# v1_0.net
KiCad netlist of a schematic drawn in Altium Designer
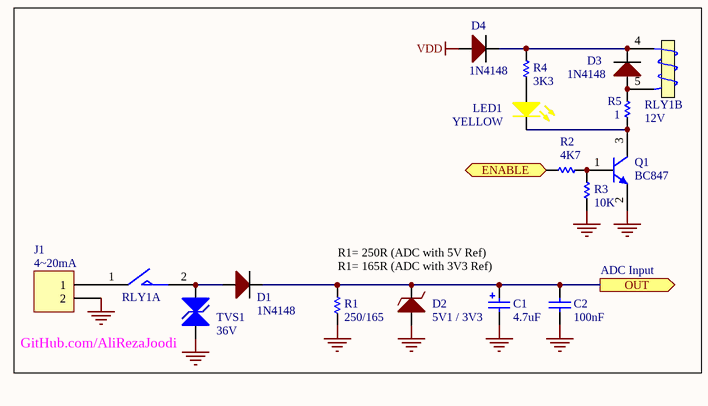
[diagram p0: v1.0.SchDoc]

(export (version "E")
  (design (tool "Eeschema 10.0.6"))
  (components
    (comp (ref "C1")
      (value "4.7uF")
      (footprint "CAPPR2.5-6.3x5")
      (description "Polarized Capacitor (Radial)")
      (fields (field (name "MANUFACTURER") "Generic Components") (field (name "PUBLISHER") "Altium Limited"))
      (libsource (lib "Miscellaneous Devices") (part "Cap Pol1"))
    )
    (comp (ref "C2")
      (value "100nF")
      (footprint "CAPNTO2.54-3.05x1.78A")
      (description "Capacitor")
      (fields (field (name "MANUFACTURER") "Generic Components") (field (name "PUBLISHER") "Altium Limited"))
      (libsource (lib "Miscellaneous Devices") (part "Cap"))
    )
    (comp (ref "D1")
      (value "1N4148")
      (footprint "D_THD_AXIAL0.3_DO-35")
      (description "Diode,")
      (libsource (lib "Passive") (part "Diode_2Form"))
    )
    (comp (ref "D2")
      (value "5V1 / 3V3")
      (footprint "D_THD_AXIAL0.3_DO-35")
      (description "Diode, Zener")
      (libsource (lib "Passive") (part "Diode_Zener"))
    )
    (comp (ref "D3")
      (value "1N4148")
      (footprint "D_THD_AXIAL0.3_DO-35")
      (description "Diode,")
      (libsource (lib "Passive") (part "Diode_2Form"))
    )
    (comp (ref "D4")
      (value "1N4148")
      (footprint "D_THD_AXIAL0.3_DO-35")
      (description "Diode,")
      (libsource (lib "Passive") (part "Diode_2Form"))
    )
    (comp (ref "J1")
      (value "Header 2")
      (footprint "Fonics_2PIN_1")
      (description "Header, 2-Pin")
      (fields (field (name "PUBLISHER") "Altium Limited"))
      (libsource (lib "Miscellaneous Connectors") (part "Header 2"))
    )
    (comp (ref "LED1")
      (value "YELLOW")
      (footprint "LED_THD_3MM_YELLOW_R")
      (description "LED, Yellow")
      (fields (field (name "MANUFACTURER") "Generic Components") (field (name "PUBLISHER") "Altium Limited"))
      (libsource (lib "Display") (part "LED_YELLOW"))
    )
    (comp (ref "Q1")
      (value "Q1")
      (footprint "SOT23-3N")
      (description "Silicon Bipolar Transistor")
      (fields (field (name "ALTIUM_VALUE") "BC847"))
      (libsource (lib "my Libraries") (part "BC847"))
    )
    (comp (ref "R1")
      (value "250/165")
      (footprint "R_THD_AXIAL0.4(1/4W)")
      (description "Resistor")
      (libsource (lib "Passive") (part "Resistor"))
    )
    (comp (ref "R2")
      (value "4K7")
      (footprint "R_THD_AXIAL0.4(1/4W)")
      (description "Resistor")
      (libsource (lib "Passive") (part "Resistor"))
    )
    (comp (ref "R3")
      (value "10K")
      (footprint "R_THD_AXIAL0.4(1/4W)")
      (description "Resistor")
      (libsource (lib "Passive") (part "Resistor"))
    )
    (comp (ref "R4")
      (value "3K3")
      (footprint "R_THD_AXIAL0.4(1/4W)")
      (description "Resistor")
      (libsource (lib "Passive") (part "Resistor"))
    )
    (comp (ref "R5")
      (value "1")
      (footprint "R_THD_AXIAL0.4(1/4W)")
      (description "Resistor")
      (libsource (lib "Passive") (part "Resistor"))
    )
    (comp (ref "RLY1")
      (value "RELAU")
      (footprint "RELAY-SPDT-2")
      (fields (field (name "PUBLISHER") "Altium Limited"))
      (libsource (lib "my Libraries") (part "RELAY-NY12W-K"))
    )
    (comp (ref "TVS1")
      (value "36V")
      (footprint "D_THD_AXIAL0.6_DO-27_DO-201A_2Form")
      (description "Diode, TVS")
      (libsource (lib "Passive") (part "Diode_TVS"))
    )
  )
  (nets
    (net (code "1") (name "/ENABLE") (class "Default")
      (node (ref "R2") (pin "2") (pinfunction "2_2") (pintype "passive"))
    )
    (net (code "2") (name "/OUT") (class "Default")
      (node (ref "C1") (pin "1") (pinfunction "1_1") (pintype "passive"))
      (node (ref "C2") (pin "2") (pinfunction "2_2") (pintype "passive"))
      (node (ref "D1") (pin "2") (pinfunction "K_2") (pintype "passive"))
      (node (ref "D2") (pin "2") (pinfunction "2_2") (pintype "passive"))
      (node (ref "R1") (pin "1") (pinfunction "1_1") (pintype "passive"))
    )
    (net (code "3") (name "GND") (class "Default")
      (node (ref "C1") (pin "2") (pinfunction "2_2") (pintype "passive"))
      (node (ref "C2") (pin "1") (pinfunction "1_1") (pintype "passive"))
      (node (ref "D2") (pin "1") (pinfunction "1_1") (pintype "passive"))
      (node (ref "J1") (pin "2") (pinfunction "2_2") (pintype "passive"))
      (node (ref "Q1") (pin "2") (pinfunction "E_2") (pintype "passive"))
      (node (ref "R1") (pin "2") (pinfunction "2_2") (pintype "passive"))
      (node (ref "R3") (pin "1") (pinfunction "1_1") (pintype "passive"))
      (node (ref "TVS1") (pin "1") (pinfunction "1_1") (pintype "passive"))
    )
    (net (code "4") (name "Net-(D1-A)") (class "Default")
      (node (ref "D1") (pin "1") (pinfunction "A_1") (pintype "passive"))
      (node (ref "RLY1") (pin "2") (pinfunction "NO_2") (pintype "passive"))
      (node (ref "TVS1") (pin "2") (pinfunction "2_2") (pintype "passive"))
    )
    (net (code "5") (name "Net-(D3-A)") (class "Default")
      (node (ref "D3") (pin "1") (pinfunction "A_1") (pintype "passive"))
      (node (ref "R5") (pin "1") (pinfunction "1_1") (pintype "passive"))
      (node (ref "RLY1") (pin "5") (pinfunction "T2_5") (pintype "passive"))
    )
    (net (code "6") (name "Net-(D3-K)") (class "Default")
      (node (ref "D3") (pin "2") (pinfunction "K_2") (pintype "passive"))
      (node (ref "D4") (pin "2") (pinfunction "K_2") (pintype "passive"))
      (node (ref "R4") (pin "2") (pinfunction "2_2") (pintype "passive"))
      (node (ref "RLY1") (pin "4") (pinfunction "T1_4") (pintype "passive"))
    )
    (net (code "7") (name "Net-(LED1-A)") (class "Default")
      (node (ref "LED1") (pin "1") (pinfunction "A_1") (pintype "passive"))
      (node (ref "R4") (pin "1") (pinfunction "1_1") (pintype "passive"))
    )
    (net (code "8") (name "Net-(LED1-K)") (class "Default")
      (node (ref "LED1") (pin "2") (pinfunction "K_2") (pintype "passive"))
      (node (ref "Q1") (pin "3") (pinfunction "C_3") (pintype "passive"))
      (node (ref "R5") (pin "2") (pinfunction "2_2") (pintype "passive"))
    )
    (net (code "9") (name "Net-(Q1-B)") (class "Default")
      (node (ref "Q1") (pin "1") (pinfunction "B_1") (pintype "passive"))
      (node (ref "R2") (pin "1") (pinfunction "1_1") (pintype "passive"))
      (node (ref "R3") (pin "2") (pinfunction "2_2") (pintype "passive"))
    )
    (net (code "10") (name "Net-(RLY1A-COM)") (class "Default")
      (node (ref "J1") (pin "1") (pinfunction "1_1") (pintype "passive"))
      (node (ref "RLY1") (pin "1") (pinfunction "COM_1") (pintype "passive"))
    )
    (net (code "11") (name "VDD") (class "Default")
      (node (ref "D4") (pin "1") (pinfunction "A_1") (pintype "passive"))
    )
  )
)
